# FPGA_SPI_interface.net
KiCad netlist of a schematic drawn in Altium Designer
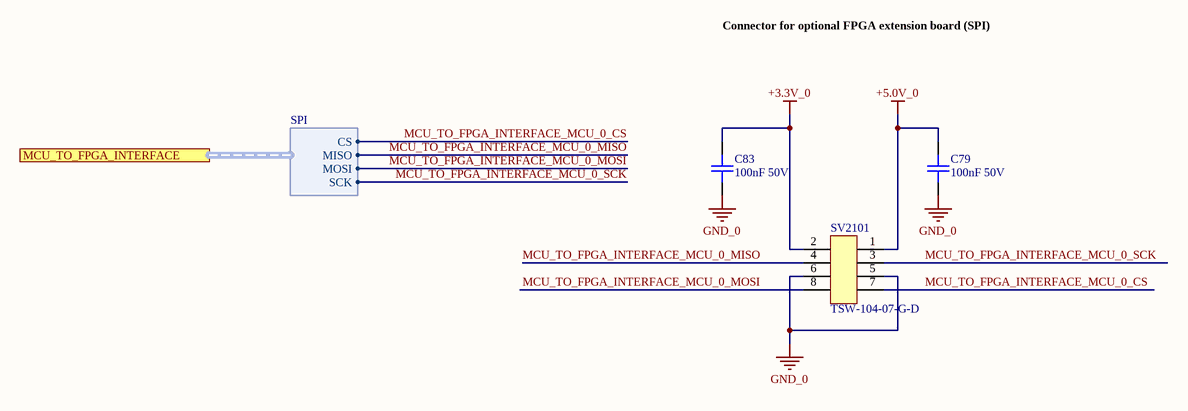
[diagram p0: FPGA_SPI_interface.SchDoc]

(export (version "E")
  (design (tool "Eeschema 10.0.6"))
  (components
    (comp (ref "C79")
      (value "100nF 50V")
      (footprint "0603C")
      (description "Ceramic, 100nF, ±10%, 50V, X7R, –55 to 125°C, 0603 (1608),RoHS, Automotive")
      (fields (field (name "PART NUMBER") "GCJ188R71H104KA12") (field (name "TOLERANCE") "±10%"))
      (libsource (lib "master-010106") (part "C"))
    )
    (comp (ref "C83")
      (value "100nF 50V")
      (footprint "0603C")
      (description "Ceramic, 100nF, ±10%, 50V, X7R, –55 to 125°C, 0603 (1608),RoHS, Automotive")
      (fields (field (name "PART NUMBER") "GCJ188R71H104KA12") (field (name "TOLERANCE") "±10%"))
      (libsource (lib "master-010106") (part "C"))
    )
    (comp (ref "SV2101")
      (value "TSW-104-07-G-D")
      (footprint "Pinheader_2.54_2x4")
      (description "Board-To-Board Connector, Vertical, 2.54 mm, 8 Contacts, Header, TSW Series, Through Hole, 2 Rows")
      (fields (field (name "MANUFACTURER") "Samtec"))
      (libsource (lib "OE750") (part "X2x4"))
    )
  )
  (nets
    (net (code "2") (name "+3.3V_0") (class "Default")
      (node (ref "C83") (pin "2") (pinfunction "2_2") (pintype "passive"))
      (node (ref "SV2101") (pin "2") (pintype "passive"))
    )
    (net (code "3") (name "+5.0V_0") (class "Default")
      (node (ref "C79") (pin "1") (pinfunction "1_1") (pintype "passive"))
      (node (ref "SV2101") (pin "1") (pintype "passive"))
    )
    (net (code "4") (name "/MCU_TO_FPGA_INTERFACE_MCU_0_CS") (class "Default")
      (node (ref "SV2101") (pin "7") (pintype "passive"))
    )
    (net (code "5") (name "/MCU_TO_FPGA_INTERFACE_MCU_0_MISO") (class "Default")
      (node (ref "SV2101") (pin "4") (pintype "passive"))
    )
    (net (code "6") (name "/MCU_TO_FPGA_INTERFACE_MCU_0_MOSI") (class "Default")
      (node (ref "SV2101") (pin "8") (pintype "passive"))
    )
    (net (code "7") (name "/MCU_TO_FPGA_INTERFACE_MCU_0_SCK") (class "Default")
      (node (ref "SV2101") (pin "3") (pintype "passive"))
    )
    (net (code "9") (name "GND_0") (class "Default")
      (node (ref "C79") (pin "2") (pinfunction "2_2") (pintype "passive"))
      (node (ref "C83") (pin "1") (pinfunction "1_1") (pintype "passive"))
      (node (ref "SV2101") (pin "5") (pintype "passive"))
      (node (ref "SV2101") (pin "6") (pintype "passive"))
    )
  )
)
